# 03-GPS_DaughterCards.net
KiCad netlist of a schematic drawn in Altium Designer
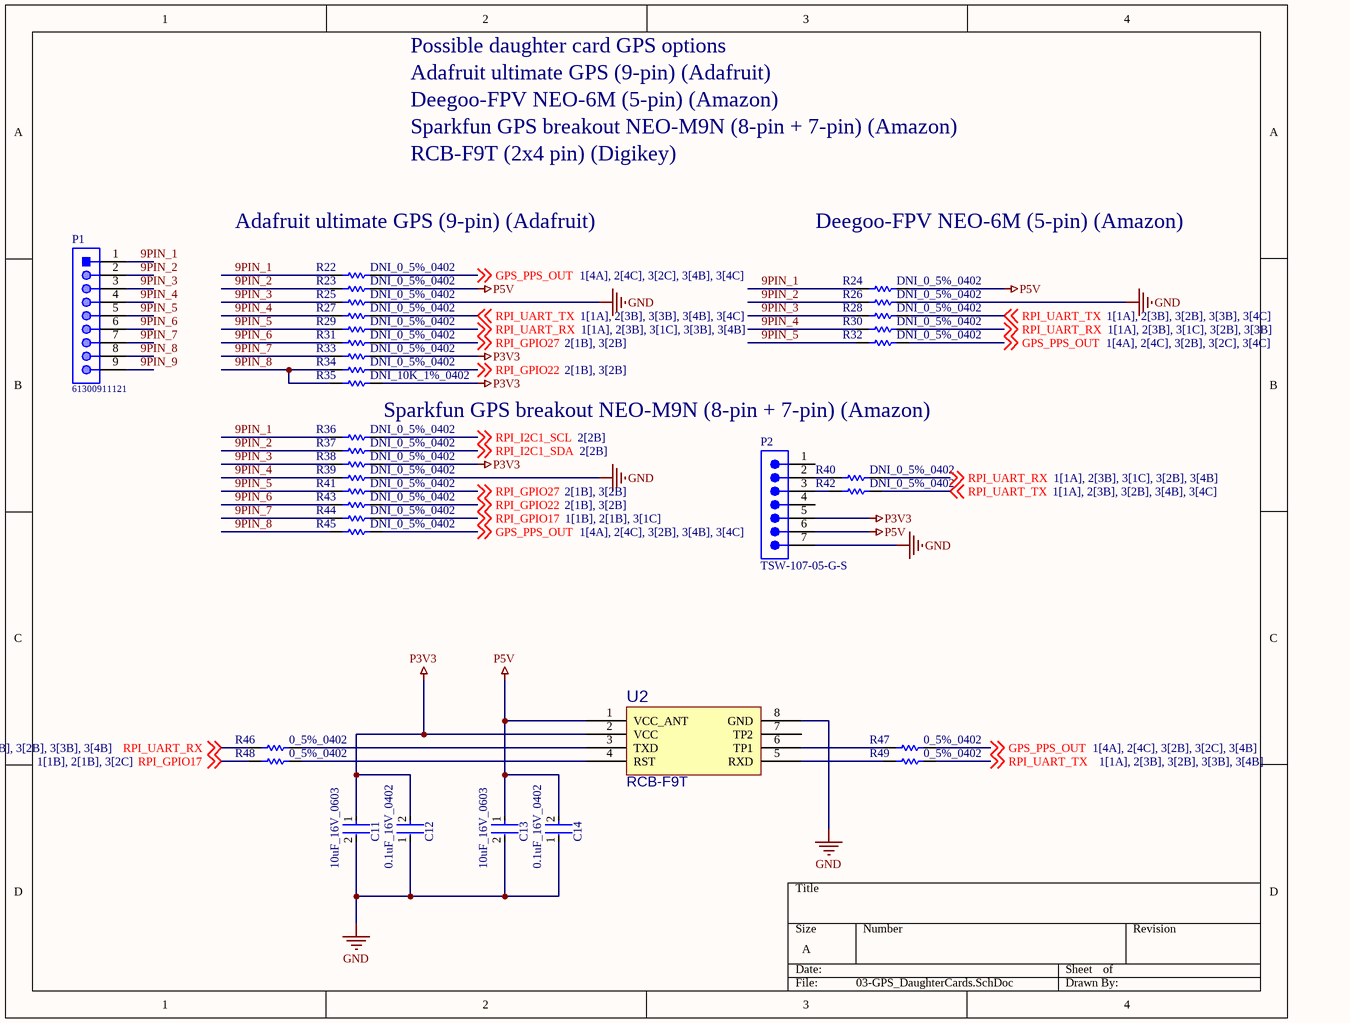
[diagram p0: 03-GPS_DaughterCards.SchDoc]

(export (version "E")
  (design (tool "Eeschema 10.0.6"))
  (components
    (comp (ref "C11")
      (value "10uF_16V_0603")
      (footprint "FP-0603-L_1_6_0_2-W_0_8_0-MFG")
      (description "Multilayer Ceramic Capacitor 10uF 16V X5R 20% SMD 0603 T/R")
      (fields (field (name "TOLERANCE") "20%"))
      (libsource (lib "Altium Content Vault") (part "b4654b650e69147ec39a6b967a45e02"))
    )
    (comp (ref "C12")
      (value "0.1uF_16V_0402")
      (footprint "FP-GRM15-MFG")
      (description "CAP CER 0.1UF 16V X7R 0402")
      (fields (field (name "MANUFACTURER PART NUMBER") "GRM155R71C104KA88D") (field (name "TOLERANCE") "10%"))
      (libsource (lib "Altium Content Vault") (part "236180d848d6139a670b325ea6854c9"))
    )
    (comp (ref "C13")
      (value "10uF_16V_0603")
      (footprint "FP-0603-L_1_6_0_2-W_0_8_0-MFG")
      (description "Multilayer Ceramic Capacitor 10uF 16V X5R 20% SMD 0603 T/R")
      (fields (field (name "TOLERANCE") "20%"))
      (libsource (lib "Altium Content Vault") (part "b4654b650e69147ec39a6b967a45e02"))
    )
    (comp (ref "C14")
      (value "0.1uF_16V_0402")
      (footprint "FP-GRM15-MFG")
      (description "CAP CER 0.1UF 16V X7R 0402")
      (fields (field (name "MANUFACTURER PART NUMBER") "GRM155R71C104KA88D") (field (name "TOLERANCE") "10%"))
      (libsource (lib "Altium Content Vault") (part "236180d848d6139a670b325ea6854c9"))
    )
    (comp (ref "P1")
      (value "61300911121")
      (footprint "61300911121")
      (description "THT Vertical Pin Header WR-PHD, Pitch 2.54 mm, Single Row, 9 pins")
      (fields (field (name "MANUFACTURER") "Wurth Elektronik") (field (name "PUBLISHER") "WurthElektronik"))
      (libsource (lib "Altium Content Vault") (part "WE-CN-1P-M-R9"))
    )
    (comp (ref "P2")
      (value "TSW-107-05-G-S")
      (footprint "SMTC-TSW-107-05-X-S")
      (description "0.025\" SQ Post Header, Through-hole, Vertical, -55 to 125 degC, 2.54 mm Pitch, 7-Pin, Male, RoHS")
      (fields (field (name "MANUFACTURER") "Samtec"))
      (libsource (lib "Altium Content Vault") (part "SMTC-TSW-107-05-X-S"))
    )
    (comp (ref "R22")
      (value "DNI_0_5%_0402")
      (footprint "RESC1005X40X25NL05T10")
      (fields (field (name "MANUFACTURER") "Yageo / Phycomp") (field (name "PART NUMBER") "RC0402JR-070RL"))
      (libsource (lib "Altium Content Vault") (part "RES"))
    )
    (comp (ref "R23")
      (value "DNI_0_5%_0402")
      (footprint "RESC1005X40X25NL05T10")
      (fields (field (name "MANUFACTURER") "Yageo / Phycomp") (field (name "PART NUMBER") "RC0402JR-070RL"))
      (libsource (lib "Altium Content Vault") (part "RES"))
    )
    (comp (ref "R24")
      (value "DNI_0_5%_0402")
      (footprint "RESC1005X40X25NL05T10")
      (fields (field (name "MANUFACTURER") "Yageo / Phycomp") (field (name "PART NUMBER") "RC0402JR-070RL"))
      (libsource (lib "Altium Content Vault") (part "RES"))
    )
    (comp (ref "R25")
      (value "DNI_0_5%_0402")
      (footprint "RESC1005X40X25NL05T10")
      (fields (field (name "MANUFACTURER") "Yageo / Phycomp") (field (name "PART NUMBER") "RC0402JR-070RL"))
      (libsource (lib "Altium Content Vault") (part "RES"))
    )
    (comp (ref "R26")
      (value "DNI_0_5%_0402")
      (footprint "RESC1005X40X25NL05T10")
      (fields (field (name "MANUFACTURER") "Yageo / Phycomp") (field (name "PART NUMBER") "RC0402JR-070RL"))
      (libsource (lib "Altium Content Vault") (part "RES"))
    )
    (comp (ref "R27")
      (value "DNI_0_5%_0402")
      (footprint "RESC1005X40X25NL05T10")
      (fields (field (name "MANUFACTURER") "Yageo / Phycomp") (field (name "PART NUMBER") "RC0402JR-070RL"))
      (libsource (lib "Altium Content Vault") (part "RES"))
    )
    (comp (ref "R28")
      (value "DNI_0_5%_0402")
      (footprint "RESC1005X40X25NL05T10")
      (fields (field (name "MANUFACTURER") "Yageo / Phycomp") (field (name "PART NUMBER") "RC0402JR-070RL"))
      (libsource (lib "Altium Content Vault") (part "RES"))
    )
    (comp (ref "R29")
      (value "DNI_0_5%_0402")
      (footprint "RESC1005X40X25NL05T10")
      (fields (field (name "MANUFACTURER") "Yageo / Phycomp") (field (name "PART NUMBER") "RC0402JR-070RL"))
      (libsource (lib "Altium Content Vault") (part "RES"))
    )
    (comp (ref "R30")
      (value "DNI_0_5%_0402")
      (footprint "RESC1005X40X25NL05T10")
      (fields (field (name "MANUFACTURER") "Yageo / Phycomp") (field (name "PART NUMBER") "RC0402JR-070RL"))
      (libsource (lib "Altium Content Vault") (part "RES"))
    )
    (comp (ref "R31")
      (value "DNI_0_5%_0402")
      (footprint "RESC1005X40X25NL05T10")
      (fields (field (name "MANUFACTURER") "Yageo / Phycomp") (field (name "PART NUMBER") "RC0402JR-070RL"))
      (libsource (lib "Altium Content Vault") (part "RES"))
    )
    (comp (ref "R32")
      (value "DNI_0_5%_0402")
      (footprint "RESC1005X40X25NL05T10")
      (fields (field (name "MANUFACTURER") "Yageo / Phycomp") (field (name "PART NUMBER") "RC0402JR-070RL"))
      (libsource (lib "Altium Content Vault") (part "RES"))
    )
    (comp (ref "R33")
      (value "DNI_0_5%_0402")
      (footprint "RESC1005X40X25NL05T10")
      (fields (field (name "MANUFACTURER") "Yageo / Phycomp") (field (name "PART NUMBER") "RC0402JR-070RL"))
      (libsource (lib "Altium Content Vault") (part "RES"))
    )
    (comp (ref "R34")
      (value "DNI_0_5%_0402")
      (footprint "RESC1005X40X25NL05T10")
      (fields (field (name "MANUFACTURER") "Yageo / Phycomp") (field (name "PART NUMBER") "RC0402JR-070RL"))
      (libsource (lib "Altium Content Vault") (part "RES"))
    )
    (comp (ref "R35")
      (value "DNI_10K_1%_0402")
      (footprint "RESC1005X40X25LL05T05")
      (description "Chip Resistor, 10 KOhm, +/- 1%, 0.1 W, -55 to 155 degC, 0402 (1005 Metric), RoHS, Tape and Reel")
      (fields (field (name "TOLERANCE") "1%") (field (name "MANUFACTURER") "Panasonic"))
      (libsource (lib "Altium Content Vault") (part "RES-2"))
    )
    (comp (ref "R36")
      (value "DNI_0_5%_0402")
      (footprint "RESC1005X40X25NL05T10")
      (fields (field (name "MANUFACTURER") "Yageo / Phycomp") (field (name "PART NUMBER") "RC0402JR-070RL"))
      (libsource (lib "Altium Content Vault") (part "RES"))
    )
    (comp (ref "R37")
      (value "DNI_0_5%_0402")
      (footprint "RESC1005X40X25NL05T10")
      (fields (field (name "MANUFACTURER") "Yageo / Phycomp") (field (name "PART NUMBER") "RC0402JR-070RL"))
      (libsource (lib "Altium Content Vault") (part "RES"))
    )
    (comp (ref "R38")
      (value "DNI_0_5%_0402")
      (footprint "RESC1005X40X25NL05T10")
      (fields (field (name "MANUFACTURER") "Yageo / Phycomp") (field (name "PART NUMBER") "RC0402JR-070RL"))
      (libsource (lib "Altium Content Vault") (part "RES"))
    )
    (comp (ref "R39")
      (value "DNI_0_5%_0402")
      (footprint "RESC1005X40X25NL05T10")
      (fields (field (name "MANUFACTURER") "Yageo / Phycomp") (field (name "PART NUMBER") "RC0402JR-070RL"))
      (libsource (lib "Altium Content Vault") (part "RES"))
    )
    (comp (ref "R40")
      (value "DNI_0_5%_0402")
      (footprint "RESC1005X40X25NL05T10")
      (fields (field (name "MANUFACTURER") "Yageo / Phycomp") (field (name "PART NUMBER") "RC0402JR-070RL"))
      (libsource (lib "Altium Content Vault") (part "RES"))
    )
    (comp (ref "R41")
      (value "DNI_0_5%_0402")
      (footprint "RESC1005X40X25NL05T10")
      (fields (field (name "MANUFACTURER") "Yageo / Phycomp") (field (name "PART NUMBER") "RC0402JR-070RL"))
      (libsource (lib "Altium Content Vault") (part "RES"))
    )
    (comp (ref "R42")
      (value "DNI_0_5%_0402")
      (footprint "RESC1005X40X25NL05T10")
      (fields (field (name "MANUFACTURER") "Yageo / Phycomp") (field (name "PART NUMBER") "RC0402JR-070RL"))
      (libsource (lib "Altium Content Vault") (part "RES"))
    )
    (comp (ref "R43")
      (value "DNI_0_5%_0402")
      (footprint "RESC1005X40X25NL05T10")
      (fields (field (name "MANUFACTURER") "Yageo / Phycomp") (field (name "PART NUMBER") "RC0402JR-070RL"))
      (libsource (lib "Altium Content Vault") (part "RES"))
    )
    (comp (ref "R44")
      (value "DNI_0_5%_0402")
      (footprint "RESC1005X40X25NL05T10")
      (fields (field (name "MANUFACTURER") "Yageo / Phycomp") (field (name "PART NUMBER") "RC0402JR-070RL"))
      (libsource (lib "Altium Content Vault") (part "RES"))
    )
    (comp (ref "R45")
      (value "DNI_0_5%_0402")
      (footprint "RESC1005X40X25NL05T10")
      (fields (field (name "MANUFACTURER") "Yageo / Phycomp") (field (name "PART NUMBER") "RC0402JR-070RL"))
      (libsource (lib "Altium Content Vault") (part "RES"))
    )
    (comp (ref "R46")
      (value "0_5%_0402")
      (footprint "RESC1005X40X25NL05T10")
      (fields (field (name "MANUFACTURER") "Yageo / Phycomp") (field (name "PART NUMBER") "RC0402JR-070RL"))
      (libsource (lib "Altium Content Vault") (part "RES"))
    )
    (comp (ref "R47")
      (value "0_5%_0402")
      (footprint "RESC1005X40X25NL05T10")
      (fields (field (name "MANUFACTURER") "Yageo / Phycomp") (field (name "PART NUMBER") "RC0402JR-070RL"))
      (libsource (lib "Altium Content Vault") (part "RES"))
    )
    (comp (ref "R48")
      (value "0_5%_0402")
      (footprint "RESC1005X40X25NL05T10")
      (fields (field (name "MANUFACTURER") "Yageo / Phycomp") (field (name "PART NUMBER") "RC0402JR-070RL"))
      (libsource (lib "Altium Content Vault") (part "RES"))
    )
    (comp (ref "R49")
      (value "0_5%_0402")
      (footprint "RESC1005X40X25NL05T10")
      (fields (field (name "MANUFACTURER") "Yageo / Phycomp") (field (name "PART NUMBER") "RC0402JR-070RL"))
      (libsource (lib "Altium Content Vault") (part "RES"))
    )
    (comp (ref "U2")
      (value "RCB-F9T")
      (footprint "GNSS")
      (description "MOD, GPS")
      (fields (field (name "VELENTIUM PART NUM") "<V PART NUM>"))
      (libsource (lib "Modules") (part "RCB-F9T"))
    )
  )
  (nets
    (net (code "1") (name "/9PIN_1") (class "Default")
      (node (ref "P1") (pin "1") (pinfunction "1_1") (pintype "passive"))
      (node (ref "R22") (pin "1") (pinfunction "1_1") (pintype "passive"))
      (node (ref "R24") (pin "1") (pinfunction "1_1") (pintype "passive"))
      (node (ref "R36") (pin "1") (pinfunction "1_1") (pintype "passive"))
    )
    (net (code "2") (name "/9PIN_2") (class "Default")
      (node (ref "P1") (pin "2") (pinfunction "2_2") (pintype "passive"))
      (node (ref "R23") (pin "1") (pinfunction "1_1") (pintype "passive"))
      (node (ref "R26") (pin "1") (pinfunction "1_1") (pintype "passive"))
      (node (ref "R37") (pin "1") (pinfunction "1_1") (pintype "passive"))
    )
    (net (code "3") (name "/9PIN_3") (class "Default")
      (node (ref "P1") (pin "3") (pinfunction "3_3") (pintype "passive"))
      (node (ref "R25") (pin "1") (pinfunction "1_1") (pintype "passive"))
      (node (ref "R28") (pin "1") (pinfunction "1_1") (pintype "passive"))
      (node (ref "R38") (pin "1") (pinfunction "1_1") (pintype "passive"))
    )
    (net (code "4") (name "/9PIN_4") (class "Default")
      (node (ref "P1") (pin "4") (pinfunction "4_4") (pintype "passive"))
      (node (ref "R27") (pin "1") (pinfunction "1_1") (pintype "passive"))
      (node (ref "R30") (pin "1") (pinfunction "1_1") (pintype "passive"))
      (node (ref "R39") (pin "1") (pinfunction "1_1") (pintype "passive"))
    )
    (net (code "5") (name "/9PIN_5") (class "Default")
      (node (ref "P1") (pin "5") (pinfunction "5_5") (pintype "passive"))
      (node (ref "R29") (pin "1") (pinfunction "1_1") (pintype "passive"))
      (node (ref "R32") (pin "1") (pinfunction "1_1") (pintype "passive"))
      (node (ref "R41") (pin "1") (pinfunction "1_1") (pintype "passive"))
    )
    (net (code "6") (name "/9PIN_6") (class "Default")
      (node (ref "P1") (pin "6") (pinfunction "6_6") (pintype "passive"))
      (node (ref "R31") (pin "1") (pinfunction "1_1") (pintype "passive"))
      (node (ref "R43") (pin "1") (pinfunction "1_1") (pintype "passive"))
    )
    (net (code "7") (name "/9PIN_7") (class "Default")
      (node (ref "P1") (pin "7") (pinfunction "7_7") (pintype "passive"))
      (node (ref "R33") (pin "1") (pinfunction "1_1") (pintype "passive"))
      (node (ref "R44") (pin "1") (pinfunction "1_1") (pintype "passive"))
    )
    (net (code "8") (name "/9PIN_8") (class "Default")
      (node (ref "P1") (pin "8") (pinfunction "8_8") (pintype "passive"))
      (node (ref "R34") (pin "1") (pinfunction "1_1") (pintype "passive"))
      (node (ref "R35") (pin "1") (pinfunction "1_1") (pintype "passive"))
      (node (ref "R45") (pin "1") (pinfunction "1_1") (pintype "passive"))
    )
    (net (code "9") (name "/9PIN_9") (class "Default")
      (node (ref "P1") (pin "9") (pinfunction "9_9") (pintype "passive"))
    )
    (net (code "10") (name "GND") (class "Default")
      (node (ref "C11") (pin "2") (pinfunction "2_2") (pintype "passive"))
      (node (ref "C12") (pin "1") (pinfunction "1_1") (pintype "passive"))
      (node (ref "C13") (pin "2") (pinfunction "2_2") (pintype "passive"))
      (node (ref "C14") (pin "1") (pinfunction "1_1") (pintype "passive"))
      (node (ref "P2") (pin "7") (pinfunction "7_7") (pintype "passive"))
      (node (ref "R25") (pin "2") (pinfunction "2_2") (pintype "passive"))
      (node (ref "R26") (pin "2") (pinfunction "2_2") (pintype "passive"))
      (node (ref "R39") (pin "2") (pinfunction "2_2") (pintype "passive"))
      (node (ref "U2") (pin "8") (pinfunction "GND_8") (pintype "passive"))
    )
    (net (code "11") (name "GPS_PPS_OUT") (class "Default")
      (node (ref "R22") (pin "2") (pinfunction "2_2") (pintype "passive"))
      (node (ref "R32") (pin "2") (pinfunction "2_2") (pintype "passive"))
      (node (ref "R45") (pin "2") (pinfunction "2_2") (pintype "passive"))
      (node (ref "R47") (pin "2") (pinfunction "2_2") (pintype "passive"))
    )
    (net (code "12") (name "Net-(P2-Pad2)") (class "Default")
      (node (ref "P2") (pin "2") (pinfunction "2_2") (pintype "passive"))
      (node (ref "R40") (pin "1") (pinfunction "1_1") (pintype "passive"))
    )
    (net (code "13") (name "Net-(P2-Pad3)") (class "Default")
      (node (ref "P2") (pin "3") (pinfunction "3_3") (pintype "passive"))
      (node (ref "R42") (pin "1") (pinfunction "1_1") (pintype "passive"))
    )
    (net (code "14") (name "Net-(U2-RST)") (class "Default")
      (node (ref "R48") (pin "2") (pinfunction "2_2") (pintype "passive"))
      (node (ref "U2") (pin "4") (pinfunction "RST_4") (pintype "passive"))
    )
    (net (code "15") (name "Net-(U2-RXD)") (class "Default")
      (node (ref "R49") (pin "1") (pinfunction "1_1") (pintype "passive"))
      (node (ref "U2") (pin "5") (pinfunction "RXD_5") (pintype "passive"))
    )
    (net (code "16") (name "Net-(U2-TP1)") (class "Default")
      (node (ref "R47") (pin "1") (pinfunction "1_1") (pintype "passive"))
      (node (ref "U2") (pin "6") (pinfunction "TP1_6") (pintype "passive"))
    )
    (net (code "17") (name "Net-(U2-TXD)") (class "Default")
      (node (ref "R46") (pin "2") (pinfunction "2_2") (pintype "passive"))
      (node (ref "U2") (pin "3") (pinfunction "TXD_3") (pintype "passive"))
    )
    (net (code "18") (name "P3V3") (class "Default")
      (node (ref "C11") (pin "1") (pinfunction "1_1") (pintype "passive"))
      (node (ref "C12") (pin "2") (pinfunction "2_2") (pintype "passive"))
      (node (ref "P2") (pin "5") (pinfunction "5_5") (pintype "passive"))
      (node (ref "R33") (pin "2") (pinfunction "2_2") (pintype "passive"))
      (node (ref "R35") (pin "2") (pinfunction "2_2") (pintype "passive"))
      (node (ref "R38") (pin "2") (pinfunction "2_2") (pintype "passive"))
      (node (ref "U2") (pin "2") (pinfunction "VCC_2") (pintype "passive"))
    )
    (net (code "19") (name "P5V") (class "Default")
      (node (ref "C13") (pin "1") (pinfunction "1_1") (pintype "passive"))
      (node (ref "C14") (pin "2") (pinfunction "2_2") (pintype "passive"))
      (node (ref "P2") (pin "6") (pinfunction "6_6") (pintype "passive"))
      (node (ref "R23") (pin "2") (pinfunction "2_2") (pintype "passive"))
      (node (ref "R24") (pin "2") (pinfunction "2_2") (pintype "passive"))
      (node (ref "U2") (pin "1") (pinfunction "VCC_ANT_1") (pintype "passive"))
    )
    (net (code "20") (name "RPI_GPIO17") (class "Default")
      (node (ref "R44") (pin "2") (pinfunction "2_2") (pintype "passive"))
      (node (ref "R48") (pin "1") (pinfunction "1_1") (pintype "passive"))
    )
    (net (code "21") (name "RPI_GPIO22") (class "Default")
      (node (ref "R34") (pin "2") (pinfunction "2_2") (pintype "passive"))
      (node (ref "R43") (pin "2") (pinfunction "2_2") (pintype "passive"))
    )
    (net (code "22") (name "RPI_GPIO27") (class "Default")
      (node (ref "R31") (pin "2") (pinfunction "2_2") (pintype "passive"))
      (node (ref "R41") (pin "2") (pinfunction "2_2") (pintype "passive"))
    )
    (net (code "23") (name "RPI_I2C1_SCL") (class "Default")
      (node (ref "R36") (pin "2") (pinfunction "2_2") (pintype "passive"))
    )
    (net (code "24") (name "RPI_I2C1_SDA") (class "Default")
      (node (ref "R37") (pin "2") (pinfunction "2_2") (pintype "passive"))
    )
    (net (code "25") (name "RPI_UART_RX") (class "Default")
      (node (ref "R29") (pin "2") (pinfunction "2_2") (pintype "passive"))
      (node (ref "R30") (pin "2") (pinfunction "2_2") (pintype "passive"))
      (node (ref "R40") (pin "2") (pinfunction "2_2") (pintype "passive"))
      (node (ref "R46") (pin "1") (pinfunction "1_1") (pintype "passive"))
    )
    (net (code "26") (name "RPI_UART_TX") (class "Default")
      (node (ref "R27") (pin "2") (pinfunction "2_2") (pintype "passive"))
      (node (ref "R28") (pin "2") (pinfunction "2_2") (pintype "passive"))
      (node (ref "R42") (pin "2") (pinfunction "2_2") (pintype "passive"))
      (node (ref "R49") (pin "2") (pinfunction "2_2") (pintype "passive"))
    )
    (net (code "27") (name "unconnected-(P2-Pad1)") (class "Default")
      (node (ref "P2") (pin "1") (pinfunction "1_1") (pintype "passive"))
    )
    (net (code "28") (name "unconnected-(P2-Pad4)") (class "Default")
      (node (ref "P2") (pin "4") (pinfunction "4_4") (pintype "passive"))
    )
    (net (code "29") (name "unconnected-(U2-TP2-Pad7)") (class "Default")
      (node (ref "U2") (pin "7") (pinfunction "TP2_7") (pintype "passive"))
    )
  )
)
